# 2bttn.net
KiCad netlist of a schematic drawn in EAGLE
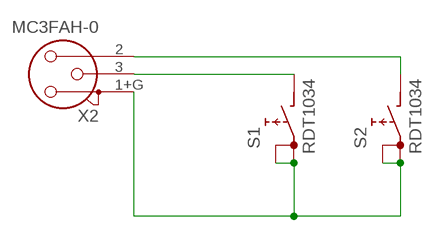
[diagram p0: schematic, sheet 1]

(export (version "E")
  (design (tool "Eeschema 10.0.6"))
  (components
    (comp (ref "S1")
      (value "RDT1034")
      (footprint "eagle-import:RDT1034")
      (libsource (lib "eagle-import") (part "RDT1034"))
    )
    (comp (ref "S2")
      (value "RDT1034")
      (footprint "eagle-import:RDT1034")
      (libsource (lib "eagle-import") (part "RDT1034"))
    )
    (comp (ref "X2")
      (value "MC3FAH-0")
      (footprint "eagle-import:NC3FAH1-0")
      (libsource (lib "eagle-import") (part "MC3?FAH-0"))
    )
  )
  (nets
    (net (code "1") (name "Net-(S1-PadB)") (class "Default")
      (node (ref "S1") (pin "B") (pinfunction "B_B") (pintype "passive"))
      (node (ref "X2") (pin "3") (pinfunction "3_3") (pintype "passive"))
    )
    (net (code "2") (name "Net-(S2-PadB)") (class "Default")
      (node (ref "S2") (pin "B") (pinfunction "B_B") (pintype "passive"))
      (node (ref "X2") (pin "2") (pinfunction "2_2") (pintype "passive"))
    )
    (net (code "3") (name "Net-(X2-1)") (class "Default")
      (node (ref "S1") (pin "A") (pinfunction "A_A") (pintype "passive"))
      (node (ref "S1") (pin "A1") (pinfunction "A1_A1") (pintype "passive"))
      (node (ref "S2") (pin "A") (pinfunction "A_A") (pintype "passive"))
      (node (ref "S2") (pin "A1") (pinfunction "A1_A1") (pintype "passive"))
      (node (ref "X2") (pin "1+G") (pinfunction "1_1+G") (pintype "passive"))
    )
  )
)
